# EN715.net
KiCad netlist of a schematic drawn in EAGLE
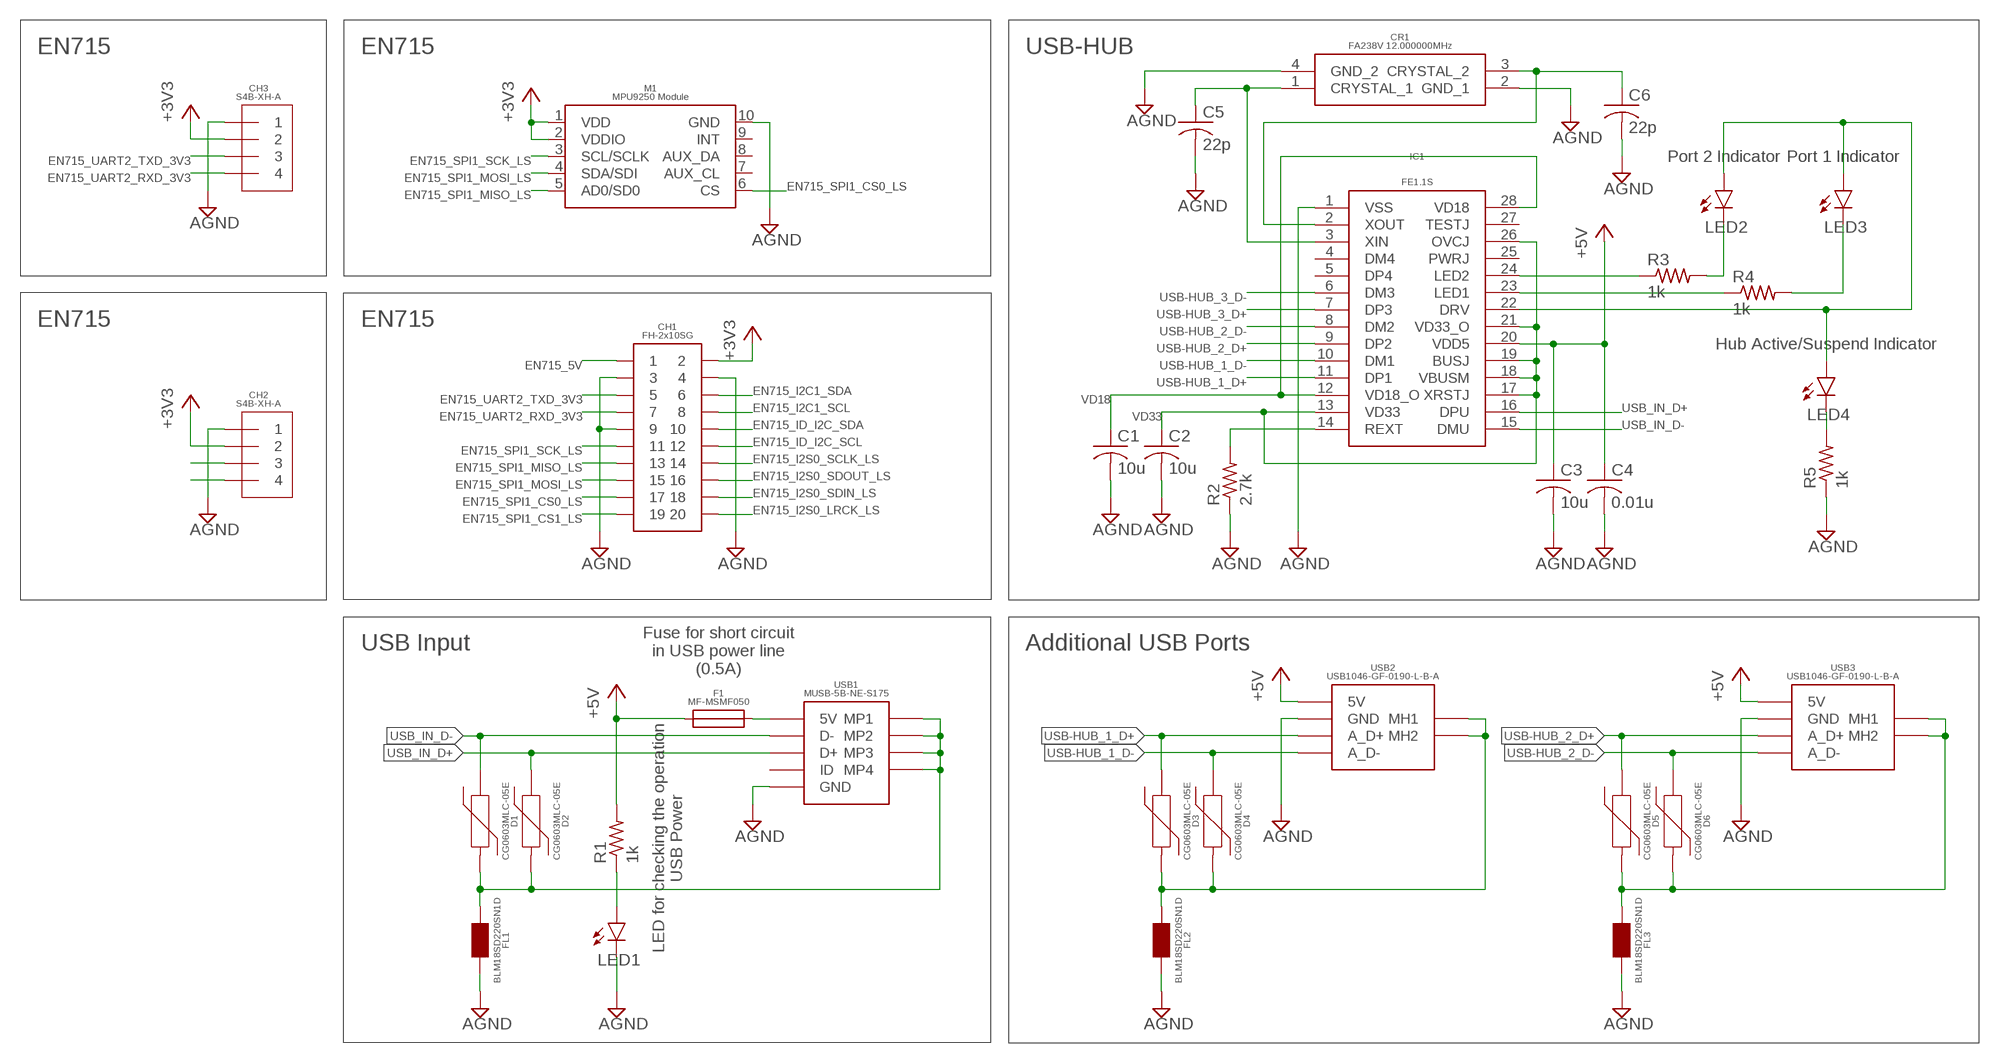
[diagram p0: schematic, sheet 1]

(export (version "E")
  (design (tool "Eeschema 10.0.6"))
  (components
    (comp (ref "C1")
      (value "10u")
      (footprint "eagle-import:C0603")
      (libsource (lib "eagle-import") (part "C-USC0603"))
    )
    (comp (ref "C2")
      (value "10u")
      (footprint "eagle-import:C0603")
      (libsource (lib "eagle-import") (part "C-USC0603"))
    )
    (comp (ref "C3")
      (value "10u")
      (footprint "eagle-import:C0603")
      (libsource (lib "eagle-import") (part "C-USC0603"))
    )
    (comp (ref "C4")
      (value "0.01u")
      (footprint "eagle-import:C0603")
      (libsource (lib "eagle-import") (part "C-USC0603"))
    )
    (comp (ref "C5")
      (value "22p")
      (footprint "eagle-import:C0603")
      (libsource (lib "eagle-import") (part "C-USC0603"))
    )
    (comp (ref "C6")
      (value "22p")
      (footprint "eagle-import:C0603")
      (libsource (lib "eagle-import") (part "C-USC0603"))
    )
    (comp (ref "CH1")
      (value "2X10")
      (footprint "eagle-import:2X10")
      (libsource (lib "eagle-import") (part "2X10"))
    )
    (comp (ref "CH2")
      (value "S4B-XH-A")
      (footprint "eagle-import:S4B-XH-A")
      (libsource (lib "eagle-import") (part "S4B-XH-A"))
    )
    (comp (ref "CH3")
      (value "S4B-XH-A")
      (footprint "eagle-import:S4B-XH-A")
      (libsource (lib "eagle-import") (part "S4B-XH-A"))
    )
    (comp (ref "CR1")
      (value "FA238V_12.000000MHZ")
      (footprint "eagle-import:FA238V")
      (libsource (lib "eagle-import") (part "FA238V_12.000000MHZ"))
    )
    (comp (ref "D1")
      (value "CG0603MLC-05E")
      (footprint "eagle-import:CG0603MLC-05E")
      (libsource (lib "eagle-import") (part "CG0603MLC-05E"))
    )
    (comp (ref "D2")
      (value "CG0603MLC-05E")
      (footprint "eagle-import:CG0603MLC-05E")
      (libsource (lib "eagle-import") (part "CG0603MLC-05E"))
    )
    (comp (ref "D3")
      (value "CG0603MLC-05E")
      (footprint "eagle-import:CG0603MLC-05E")
      (libsource (lib "eagle-import") (part "CG0603MLC-05E"))
    )
    (comp (ref "D4")
      (value "CG0603MLC-05E")
      (footprint "eagle-import:CG0603MLC-05E")
      (libsource (lib "eagle-import") (part "CG0603MLC-05E"))
    )
    (comp (ref "D5")
      (value "CG0603MLC-05E")
      (footprint "eagle-import:CG0603MLC-05E")
      (libsource (lib "eagle-import") (part "CG0603MLC-05E"))
    )
    (comp (ref "D6")
      (value "CG0603MLC-05E")
      (footprint "eagle-import:CG0603MLC-05E")
      (libsource (lib "eagle-import") (part "CG0603MLC-05E"))
    )
    (comp (ref "F1")
      (value "MF-MSMF050")
      (footprint "eagle-import:MF-MSMF050")
      (libsource (lib "eagle-import") (part "MF-MSMF050"))
    )
    (comp (ref "FL1")
      (value "BLM18SD220SN1D")
      (footprint "eagle-import:BLM18SD220SN1D")
      (libsource (lib "eagle-import") (part "BLM18SD220SN1D"))
    )
    (comp (ref "FL2")
      (value "BLM18SD220SN1D")
      (footprint "eagle-import:BLM18SD220SN1D")
      (libsource (lib "eagle-import") (part "BLM18SD220SN1D"))
    )
    (comp (ref "FL3")
      (value "BLM18SD220SN1D")
      (footprint "eagle-import:BLM18SD220SN1D")
      (libsource (lib "eagle-import") (part "BLM18SD220SN1D"))
    )
    (comp (ref "IC1")
      (value "FE1.1S")
      (footprint "eagle-import:FE1.1S")
      (libsource (lib "eagle-import") (part "FE1.1S"))
    )
    (comp (ref "LED1")
      (value "LEDSML0603")
      (footprint "eagle-import:SML0603")
      (libsource (lib "eagle-import") (part "LEDSML0603"))
    )
    (comp (ref "LED2")
      (value "LEDSML0603")
      (footprint "eagle-import:SML0603")
      (libsource (lib "eagle-import") (part "LEDSML0603"))
    )
    (comp (ref "LED3")
      (value "LEDSML0603")
      (footprint "eagle-import:SML0603")
      (libsource (lib "eagle-import") (part "LEDSML0603"))
    )
    (comp (ref "LED4")
      (value "LEDSML0603")
      (footprint "eagle-import:SML0603")
      (libsource (lib "eagle-import") (part "LEDSML0603"))
    )
    (comp (ref "M1")
      (value "MPU9250_MODULE")
      (footprint "eagle-import:MPU9250_MODULE")
      (libsource (lib "eagle-import") (part "MPU9250_MODULE"))
    )
    (comp (ref "R1")
      (value "1k")
      (footprint "eagle-import:R0603")
      (libsource (lib "eagle-import") (part "R-US_R0603"))
    )
    (comp (ref "R2")
      (value "2.7k")
      (footprint "eagle-import:R0603")
      (libsource (lib "eagle-import") (part "R-US_R0603"))
    )
    (comp (ref "R3")
      (value "1k")
      (footprint "eagle-import:R0603")
      (libsource (lib "eagle-import") (part "R-US_R0603"))
    )
    (comp (ref "R4")
      (value "1k")
      (footprint "eagle-import:R0603")
      (libsource (lib "eagle-import") (part "R-US_R0603"))
    )
    (comp (ref "R5")
      (value "1k")
      (footprint "eagle-import:R0603")
      (libsource (lib "eagle-import") (part "R-US_R0603"))
    )
    (comp (ref "USB1")
      (value "MINI_USB_B_SMD")
      (footprint "eagle-import:MINI_USB_B_SMD")
      (libsource (lib "eagle-import") (part "MINI_USB_B_SMD"))
    )
    (comp (ref "USB2")
      (value "USB_A_X1_SMD")
      (footprint "eagle-import:USB_A_X1_SMD")
      (libsource (lib "eagle-import") (part "USB_A_X1_SMD"))
    )
    (comp (ref "USB3")
      (value "USB_A_X1_SMD")
      (footprint "eagle-import:USB_A_X1_SMD")
      (libsource (lib "eagle-import") (part "USB_A_X1_SMD"))
    )
  )
  (nets
    (net (code "1") (name "+3V3") (class "Default")
      (node (ref "CH1") (pin "2") (pinfunction "2_2") (pintype "bidirectional"))
      (node (ref "CH2") (pin "2") (pinfunction "2_2") (pintype "bidirectional"))
      (node (ref "CH3") (pin "2") (pinfunction "2_2") (pintype "bidirectional"))
      (node (ref "M1") (pin "1") (pinfunction "VDD_1") (pintype "bidirectional"))
      (node (ref "M1") (pin "2") (pinfunction "VDDIO_2") (pintype "bidirectional"))
    )
    (net (code "2") (name "+5V") (class "Default")
      (node (ref "C3") (pin "1") (pinfunction "1_1") (pintype "passive"))
      (node (ref "C4") (pin "1") (pinfunction "1_1") (pintype "passive"))
      (node (ref "F1") (pin "1") (pinfunction "1_1") (pintype "bidirectional"))
      (node (ref "IC1") (pin "20") (pinfunction "VDD5_20") (pintype "bidirectional"))
      (node (ref "R1") (pin "2") (pinfunction "2_2") (pintype "passive"))
      (node (ref "USB2") (pin "1") (pinfunction "5V_1") (pintype "bidirectional"))
      (node (ref "USB3") (pin "1") (pinfunction "5V_1") (pintype "bidirectional"))
    )
    (net (code "3") (name "/EN715_5V") (class "Default")
      (node (ref "CH1") (pin "1") (pinfunction "1_1") (pintype "bidirectional"))
    )
    (net (code "4") (name "/EN715_I2C1_SCL") (class "Default")
      (node (ref "CH1") (pin "8") (pinfunction "8_8") (pintype "bidirectional"))
    )
    (net (code "5") (name "/EN715_I2C1_SDA") (class "Default")
      (node (ref "CH1") (pin "6") (pinfunction "6_6") (pintype "bidirectional"))
    )
    (net (code "6") (name "/EN715_I2S0_LRCK_LS") (class "Default")
      (node (ref "CH1") (pin "20") (pinfunction "20_20") (pintype "bidirectional"))
    )
    (net (code "7") (name "/EN715_I2S0_SCLK_LS") (class "Default")
      (node (ref "CH1") (pin "14") (pinfunction "14_14") (pintype "bidirectional"))
    )
    (net (code "8") (name "/EN715_I2S0_SDIN_LS") (class "Default")
      (node (ref "CH1") (pin "18") (pinfunction "18_18") (pintype "bidirectional"))
    )
    (net (code "9") (name "/EN715_I2S0_SDOUT_LS") (class "Default")
      (node (ref "CH1") (pin "16") (pinfunction "16_16") (pintype "bidirectional"))
    )
    (net (code "10") (name "/EN715_ID_I2C_SCL") (class "Default")
      (node (ref "CH1") (pin "12") (pinfunction "12_12") (pintype "bidirectional"))
    )
    (net (code "11") (name "/EN715_ID_I2C_SDA") (class "Default")
      (node (ref "CH1") (pin "10") (pinfunction "10_10") (pintype "bidirectional"))
    )
    (net (code "12") (name "/EN715_SPI1_CS0_LS") (class "Default")
      (node (ref "CH1") (pin "17") (pinfunction "17_17") (pintype "bidirectional"))
      (node (ref "M1") (pin "6") (pinfunction "CS_6") (pintype "bidirectional"))
    )
    (net (code "13") (name "/EN715_SPI1_CS1_LS") (class "Default")
      (node (ref "CH1") (pin "19") (pinfunction "19_19") (pintype "bidirectional"))
    )
    (net (code "14") (name "/EN715_SPI1_MISO_LS") (class "Default")
      (node (ref "CH1") (pin "13") (pinfunction "13_13") (pintype "bidirectional"))
      (node (ref "M1") (pin "5") (pinfunction "AD0/SD0_5") (pintype "bidirectional"))
    )
    (net (code "15") (name "/EN715_SPI1_MOSI_LS") (class "Default")
      (node (ref "CH1") (pin "15") (pinfunction "15_15") (pintype "bidirectional"))
      (node (ref "M1") (pin "4") (pinfunction "SDA/SDI_4") (pintype "bidirectional"))
    )
    (net (code "16") (name "/EN715_SPI1_SCK_LS") (class "Default")
      (node (ref "CH1") (pin "11") (pinfunction "11_11") (pintype "bidirectional"))
      (node (ref "M1") (pin "3") (pinfunction "SCL/SCLK_3") (pintype "bidirectional"))
    )
    (net (code "17") (name "/EN715_UART2_RXD_3V3") (class "Default")
      (node (ref "CH1") (pin "7") (pinfunction "7_7") (pintype "bidirectional"))
      (node (ref "CH3") (pin "4") (pinfunction "4_4") (pintype "bidirectional"))
    )
    (net (code "18") (name "/EN715_UART2_TXD_3V3") (class "Default")
      (node (ref "CH1") (pin "5") (pinfunction "5_5") (pintype "bidirectional"))
      (node (ref "CH3") (pin "3") (pinfunction "3_3") (pintype "bidirectional"))
    )
    (net (code "19") (name "/USB-HUB_3_D+") (class "Default")
      (node (ref "IC1") (pin "7") (pinfunction "DP3_7") (pintype "bidirectional"))
    )
    (net (code "20") (name "/USB-HUB_3_D-") (class "Default")
      (node (ref "IC1") (pin "6") (pinfunction "DM3_6") (pintype "bidirectional"))
    )
    (net (code "21") (name "/VD18") (class "Default")
      (node (ref "C1") (pin "1") (pinfunction "1_1") (pintype "passive"))
      (node (ref "IC1") (pin "12") (pinfunction "VD18_O_12") (pintype "bidirectional"))
      (node (ref "IC1") (pin "28") (pinfunction "VD18_28") (pintype "bidirectional"))
    )
    (net (code "22") (name "/VD33") (class "Default")
      (node (ref "C2") (pin "1") (pinfunction "1_1") (pintype "passive"))
      (node (ref "IC1") (pin "13") (pinfunction "VD33_13") (pintype "bidirectional"))
      (node (ref "IC1") (pin "17") (pinfunction "XRSTJ_17") (pintype "bidirectional"))
      (node (ref "IC1") (pin "18") (pinfunction "VBUSM_18") (pintype "bidirectional"))
      (node (ref "IC1") (pin "19") (pinfunction "BUSJ_19") (pintype "bidirectional"))
      (node (ref "IC1") (pin "21") (pinfunction "VD33_O_21") (pintype "bidirectional"))
      (node (ref "IC1") (pin "26") (pinfunction "OVCJ_26") (pintype "bidirectional"))
    )
    (net (code "23") (name "AGND") (class "Default")
      (node (ref "C1") (pin "2") (pinfunction "2_2") (pintype "passive"))
      (node (ref "C2") (pin "2") (pinfunction "2_2") (pintype "passive"))
      (node (ref "C3") (pin "2") (pinfunction "2_2") (pintype "passive"))
      (node (ref "C4") (pin "2") (pinfunction "2_2") (pintype "passive"))
      (node (ref "C5") (pin "2") (pinfunction "2_2") (pintype "passive"))
      (node (ref "C6") (pin "2") (pinfunction "2_2") (pintype "passive"))
      (node (ref "CH1") (pin "3") (pinfunction "3_3") (pintype "bidirectional"))
      (node (ref "CH1") (pin "4") (pinfunction "4_4") (pintype "bidirectional"))
      (node (ref "CH1") (pin "9") (pinfunction "9_9") (pintype "bidirectional"))
      (node (ref "CH2") (pin "1") (pinfunction "1_1") (pintype "bidirectional"))
      (node (ref "CH3") (pin "1") (pinfunction "1_1") (pintype "bidirectional"))
      (node (ref "CR1") (pin "2") (pinfunction "GND_1_2") (pintype "bidirectional"))
      (node (ref "CR1") (pin "4") (pinfunction "GND_2_4") (pintype "bidirectional"))
      (node (ref "FL1") (pin "2") (pinfunction "2_2") (pintype "bidirectional"))
      (node (ref "FL2") (pin "2") (pinfunction "2_2") (pintype "bidirectional"))
      (node (ref "FL3") (pin "2") (pinfunction "2_2") (pintype "bidirectional"))
      (node (ref "IC1") (pin "1") (pinfunction "VSS_1") (pintype "bidirectional"))
      (node (ref "LED1") (pin "C") (pinfunction "C_C") (pintype "passive"))
      (node (ref "M1") (pin "10") (pinfunction "GND_10") (pintype "bidirectional"))
      (node (ref "R2") (pin "1") (pinfunction "1_1") (pintype "passive"))
      (node (ref "R5") (pin "1") (pinfunction "1_1") (pintype "passive"))
      (node (ref "USB1") (pin "5") (pinfunction "GND_5") (pintype "bidirectional"))
      (node (ref "USB2") (pin "4") (pinfunction "GND_4") (pintype "bidirectional"))
      (node (ref "USB3") (pin "4") (pinfunction "GND_4") (pintype "bidirectional"))
    )
    (net (code "24") (name "Net-(CR1-CRYSTAL_1)") (class "Default")
      (node (ref "C5") (pin "1") (pinfunction "1_1") (pintype "passive"))
      (node (ref "CR1") (pin "1") (pinfunction "CRYSTAL_1_1") (pintype "bidirectional"))
      (node (ref "IC1") (pin "3") (pinfunction "XIN_3") (pintype "bidirectional"))
    )
    (net (code "25") (name "Net-(CR1-CRYSTAL_2)") (class "Default")
      (node (ref "C6") (pin "1") (pinfunction "1_1") (pintype "passive"))
      (node (ref "CR1") (pin "3") (pinfunction "CRYSTAL_2_3") (pintype "bidirectional"))
      (node (ref "IC1") (pin "2") (pinfunction "XOUT_2") (pintype "bidirectional"))
    )
    (net (code "26") (name "Net-(D1-Pad2)") (class "Default")
      (node (ref "D1") (pin "2") (pinfunction "2_2") (pintype "bidirectional"))
      (node (ref "D2") (pin "2") (pinfunction "2_2") (pintype "bidirectional"))
      (node (ref "FL1") (pin "1") (pinfunction "1_1") (pintype "bidirectional"))
      (node (ref "USB1") (pin "MP1") (pinfunction "MP1_MP1") (pintype "bidirectional"))
      (node (ref "USB1") (pin "MP2") (pinfunction "MP2_MP2") (pintype "bidirectional"))
      (node (ref "USB1") (pin "MP3") (pinfunction "MP3_MP3") (pintype "bidirectional"))
      (node (ref "USB1") (pin "MP4") (pinfunction "MP4_MP4") (pintype "bidirectional"))
    )
    (net (code "27") (name "Net-(D3-Pad2)") (class "Default")
      (node (ref "D3") (pin "2") (pinfunction "2_2") (pintype "bidirectional"))
      (node (ref "D4") (pin "2") (pinfunction "2_2") (pintype "bidirectional"))
      (node (ref "FL2") (pin "1") (pinfunction "1_1") (pintype "bidirectional"))
      (node (ref "USB2") (pin "MH1") (pinfunction "MH1_MH1") (pintype "bidirectional"))
      (node (ref "USB2") (pin "MH2") (pinfunction "MH2_MH2") (pintype "bidirectional"))
    )
    (net (code "28") (name "Net-(D5-Pad2)") (class "Default")
      (node (ref "D5") (pin "2") (pinfunction "2_2") (pintype "bidirectional"))
      (node (ref "D6") (pin "2") (pinfunction "2_2") (pintype "bidirectional"))
      (node (ref "FL3") (pin "1") (pinfunction "1_1") (pintype "bidirectional"))
      (node (ref "USB3") (pin "MH1") (pinfunction "MH1_MH1") (pintype "bidirectional"))
      (node (ref "USB3") (pin "MH2") (pinfunction "MH2_MH2") (pintype "bidirectional"))
    )
    (net (code "29") (name "Net-(IC1-DRV)") (class "Default")
      (node (ref "IC1") (pin "22") (pinfunction "DRV_22") (pintype "bidirectional"))
      (node (ref "LED2") (pin "A") (pinfunction "A_A") (pintype "passive"))
      (node (ref "LED3") (pin "A") (pinfunction "A_A") (pintype "passive"))
      (node (ref "LED4") (pin "A") (pinfunction "A_A") (pintype "passive"))
    )
    (net (code "30") (name "Net-(IC1-LED1)") (class "Default")
      (node (ref "IC1") (pin "23") (pinfunction "LED1_23") (pintype "bidirectional"))
      (node (ref "R4") (pin "1") (pinfunction "1_1") (pintype "passive"))
    )
    (net (code "31") (name "Net-(IC1-LED2)") (class "Default")
      (node (ref "IC1") (pin "24") (pinfunction "LED2_24") (pintype "bidirectional"))
      (node (ref "R3") (pin "1") (pinfunction "1_1") (pintype "passive"))
    )
    (net (code "32") (name "Net-(IC1-REXT)") (class "Default")
      (node (ref "IC1") (pin "14") (pinfunction "REXT_14") (pintype "bidirectional"))
      (node (ref "R2") (pin "2") (pinfunction "2_2") (pintype "passive"))
    )
    (net (code "33") (name "Net-(LED1-PadA)") (class "Default")
      (node (ref "LED1") (pin "A") (pinfunction "A_A") (pintype "passive"))
      (node (ref "R1") (pin "1") (pinfunction "1_1") (pintype "passive"))
    )
    (net (code "34") (name "Net-(LED2-PadC)") (class "Default")
      (node (ref "LED2") (pin "C") (pinfunction "C_C") (pintype "passive"))
      (node (ref "R3") (pin "2") (pinfunction "2_2") (pintype "passive"))
    )
    (net (code "35") (name "Net-(LED3-PadC)") (class "Default")
      (node (ref "LED3") (pin "C") (pinfunction "C_C") (pintype "passive"))
      (node (ref "R4") (pin "2") (pinfunction "2_2") (pintype "passive"))
    )
    (net (code "36") (name "Net-(LED4-PadC)") (class "Default")
      (node (ref "LED4") (pin "C") (pinfunction "C_C") (pintype "passive"))
      (node (ref "R5") (pin "2") (pinfunction "2_2") (pintype "passive"))
    )
    (net (code "37") (name "Net-(USB1-5V)") (class "Default")
      (node (ref "F1") (pin "2") (pinfunction "2_2") (pintype "bidirectional"))
      (node (ref "USB1") (pin "1") (pinfunction "5V_1") (pintype "bidirectional"))
    )
    (net (code "38") (name "USB-HUB_1_D+") (class "Default")
      (node (ref "D3") (pin "1") (pinfunction "1_1") (pintype "bidirectional"))
      (node (ref "IC1") (pin "11") (pinfunction "DP1_11") (pintype "bidirectional"))
      (node (ref "USB2") (pin "3") (pinfunction "A_D+_3") (pintype "bidirectional"))
    )
    (net (code "39") (name "USB-HUB_1_D-") (class "Default")
      (node (ref "D4") (pin "1") (pinfunction "1_1") (pintype "bidirectional"))
      (node (ref "IC1") (pin "10") (pinfunction "DM1_10") (pintype "bidirectional"))
      (node (ref "USB2") (pin "2") (pinfunction "A_D-_2") (pintype "bidirectional"))
    )
    (net (code "40") (name "USB-HUB_2_D+") (class "Default")
      (node (ref "D5") (pin "1") (pinfunction "1_1") (pintype "bidirectional"))
      (node (ref "IC1") (pin "9") (pinfunction "DP2_9") (pintype "bidirectional"))
      (node (ref "USB3") (pin "3") (pinfunction "A_D+_3") (pintype "bidirectional"))
    )
    (net (code "41") (name "USB-HUB_2_D-") (class "Default")
      (node (ref "D6") (pin "1") (pinfunction "1_1") (pintype "bidirectional"))
      (node (ref "IC1") (pin "8") (pinfunction "DM2_8") (pintype "bidirectional"))
      (node (ref "USB3") (pin "2") (pinfunction "A_D-_2") (pintype "bidirectional"))
    )
    (net (code "42") (name "USB_IN_D+") (class "Default")
      (node (ref "D2") (pin "1") (pinfunction "1_1") (pintype "bidirectional"))
      (node (ref "IC1") (pin "16") (pinfunction "DPU_16") (pintype "bidirectional"))
      (node (ref "USB1") (pin "3") (pinfunction "D+_3") (pintype "bidirectional"))
    )
    (net (code "43") (name "USB_IN_D-") (class "Default")
      (node (ref "D1") (pin "1") (pinfunction "1_1") (pintype "bidirectional"))
      (node (ref "IC1") (pin "15") (pinfunction "DMU_15") (pintype "bidirectional"))
      (node (ref "USB1") (pin "2") (pinfunction "D-_2") (pintype "bidirectional"))
    )
    (net (code "44") (name "unconnected-(CH2-Pad3)") (class "Default")
      (node (ref "CH2") (pin "3") (pinfunction "3_3") (pintype "bidirectional"))
    )
    (net (code "45") (name "unconnected-(CH2-Pad4)") (class "Default")
      (node (ref "CH2") (pin "4") (pinfunction "4_4") (pintype "bidirectional"))
    )
    (net (code "46") (name "unconnected-(IC1-DM4-Pad4)") (class "Default")
      (node (ref "IC1") (pin "4") (pinfunction "DM4_4") (pintype "bidirectional"))
    )
    (net (code "47") (name "unconnected-(IC1-DP4-Pad5)") (class "Default")
      (node (ref "IC1") (pin "5") (pinfunction "DP4_5") (pintype "bidirectional"))
    )
    (net (code "48") (name "unconnected-(IC1-PWRJ-Pad25)") (class "Default")
      (node (ref "IC1") (pin "25") (pinfunction "PWRJ_25") (pintype "bidirectional"))
    )
    (net (code "49") (name "unconnected-(IC1-TESTJ-Pad27)") (class "Default")
      (node (ref "IC1") (pin "27") (pinfunction "TESTJ_27") (pintype "bidirectional"))
    )
    (net (code "50") (name "unconnected-(M1-AUX_CL-Pad7)") (class "Default")
      (node (ref "M1") (pin "7") (pinfunction "AUX_CL_7") (pintype "bidirectional"))
    )
    (net (code "51") (name "unconnected-(M1-AUX_DA-Pad8)") (class "Default")
      (node (ref "M1") (pin "8") (pinfunction "AUX_DA_8") (pintype "bidirectional"))
    )
    (net (code "52") (name "unconnected-(M1-INT-Pad9)") (class "Default")
      (node (ref "M1") (pin "9") (pinfunction "INT_9") (pintype "bidirectional"))
    )
    (net (code "53") (name "unconnected-(USB1-ID-Pad4)") (class "Default")
      (node (ref "USB1") (pin "4") (pinfunction "ID_4") (pintype "bidirectional"))
    )
  )
)
